# NAND-X_QSB_Board_A.net
KiCad netlist of a schematic drawn in EAGLE
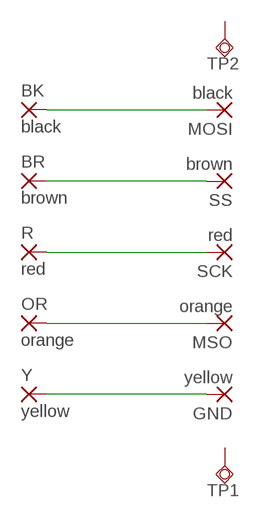
[diagram p0: schematic, sheet 1]

(export (version "E")
  (design (tool "Eeschema 10.0.6"))
  (components
    (comp (ref "BK")
      (value "black")
      (footprint "eagle-import:1,6_0,8")
      (libsource (lib "eagle-import") (part "1,6/0,8"))
    )
    (comp (ref "BR")
      (value "brown")
      (footprint "eagle-import:1,6_0,8")
      (libsource (lib "eagle-import") (part "1,6/0,8"))
    )
    (comp (ref "GND")
      (value "yellow")
      (footprint "eagle-import:SMD1,27-2,54")
      (libsource (lib "eagle-import") (part "SMD2"))
    )
    (comp (ref "MOSI")
      (value "black")
      (footprint "eagle-import:SMD1,27-2,54")
      (libsource (lib "eagle-import") (part "SMD2"))
    )
    (comp (ref "MSO")
      (value "orange")
      (footprint "eagle-import:SMD1,27-2,54")
      (libsource (lib "eagle-import") (part "SMD2"))
    )
    (comp (ref "OR")
      (value "orange")
      (footprint "eagle-import:1,6_0,8")
      (libsource (lib "eagle-import") (part "1,6/0,8"))
    )
    (comp (ref "R")
      (value "red")
      (footprint "eagle-import:1,6_0,8")
      (libsource (lib "eagle-import") (part "1,6/0,8"))
    )
    (comp (ref "SCK")
      (value "red")
      (footprint "eagle-import:SMD1,27-2,54")
      (libsource (lib "eagle-import") (part "SMD2"))
    )
    (comp (ref "SS")
      (value "brown")
      (footprint "eagle-import:SMD1,27-2,54")
      (libsource (lib "eagle-import") (part "SMD2"))
    )
    (comp (ref "TP1")
      (value "TPSQTP11SQ")
      (footprint "eagle-import:TP11SQ")
      (libsource (lib "eagle-import") (part "TPSQTP11SQ"))
    )
    (comp (ref "TP2")
      (value "TPSQTP11SQ")
      (footprint "eagle-import:TP11SQ")
      (libsource (lib "eagle-import") (part "TPSQTP11SQ"))
    )
    (comp (ref "Y")
      (value "yellow")
      (footprint "eagle-import:1,6_0,8")
      (libsource (lib "eagle-import") (part "1,6/0,8"))
    )
  )
  (nets
    (net (code "1") (name "Net-(BK-P)") (class "Default")
      (node (ref "BK") (pin "1") (pinfunction "P_1") (pintype "passive"))
      (node (ref "MOSI") (pin "1") (pinfunction "P_1") (pintype "passive"))
    )
    (net (code "2") (name "Net-(BR-P)") (class "Default")
      (node (ref "BR") (pin "1") (pinfunction "P_1") (pintype "passive"))
      (node (ref "SS") (pin "1") (pinfunction "P_1") (pintype "passive"))
    )
    (net (code "3") (name "Net-(GND-P)") (class "Default")
      (node (ref "GND") (pin "1") (pinfunction "P_1") (pintype "passive"))
      (node (ref "Y") (pin "1") (pinfunction "P_1") (pintype "passive"))
    )
    (net (code "4") (name "Net-(MSO-P)") (class "Default")
      (node (ref "MSO") (pin "1") (pinfunction "P_1") (pintype "passive"))
      (node (ref "OR") (pin "1") (pinfunction "P_1") (pintype "passive"))
    )
    (net (code "5") (name "Net-(R-P)") (class "Default")
      (node (ref "R") (pin "1") (pinfunction "P_1") (pintype "passive"))
      (node (ref "SCK") (pin "1") (pinfunction "P_1") (pintype "passive"))
    )
    (net (code "6") (name "unconnected-(TP1-PadTP)") (class "Default")
      (node (ref "TP1") (pin "TP") (pinfunction "TP_TP") (pintype "input"))
    )
    (net (code "7") (name "unconnected-(TP2-PadTP)") (class "Default")
      (node (ref "TP2") (pin "TP") (pinfunction "TP_TP") (pintype "input"))
    )
  )
)
